# BatteryHullBoard.net
KiCad netlist of a schematic drawn in EAGLE
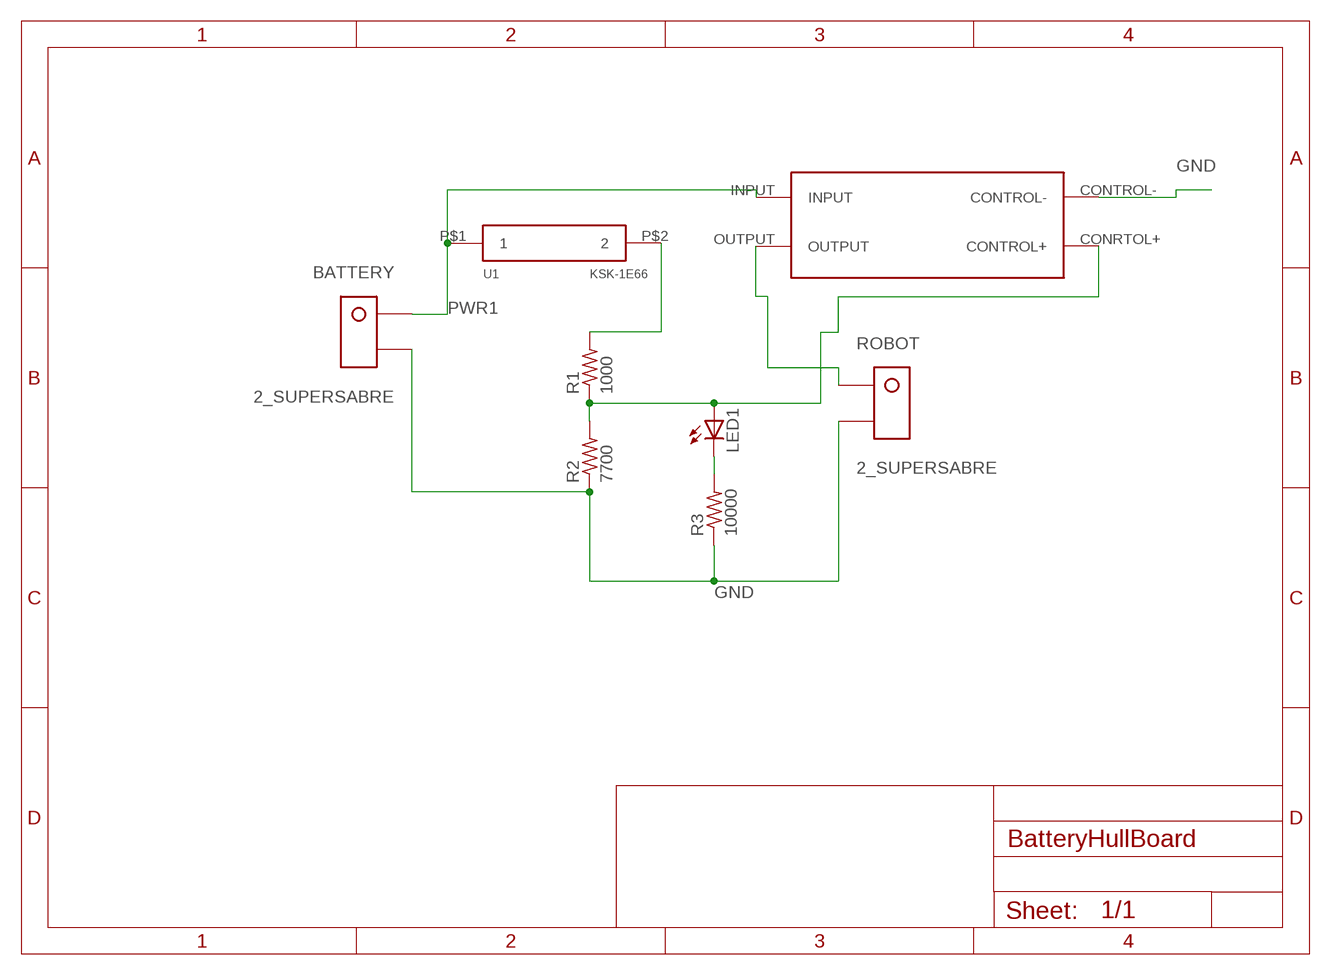
[diagram p0: schematic, sheet 1]

(export (version "E")
  (design (tool "Eeschema 10.0.6"))
  (components
    (comp (ref "BATTERY")
      (value "2_SUPERSABRE")
      (footprint "eagle-import:SUPERSABRE_2CIRCUIT")
      (libsource (lib "eagle-import") (part "2_SUPERSABRE"))
    )
    (comp (ref "LED1")
      (value "LED5MM")
      (footprint "eagle-import:LED5MM")
      (libsource (lib "eagle-import") (part "LED5MM"))
    )
    (comp (ref "R1")
      (value "1000")
      (footprint "eagle-import:R0805")
      (libsource (lib "eagle-import") (part "R-US_R0805"))
    )
    (comp (ref "R2")
      (value "7700")
      (footprint "eagle-import:R0805")
      (libsource (lib "eagle-import") (part "R-US_R0805"))
    )
    (comp (ref "R3")
      (value "10000")
      (footprint "eagle-import:R0805")
      (libsource (lib "eagle-import") (part "R-US_R0805"))
    )
    (comp (ref "ROBOT")
      (value "2_SUPERSABRE")
      (footprint "eagle-import:SUPERSABRE_2CIRCUIT")
      (libsource (lib "eagle-import") (part "2_SUPERSABRE"))
    )
    (comp (ref "U$1")
      (value "ADJH21112")
      (footprint "eagle-import:ADJH21112")
      (libsource (lib "eagle-import") (part "ADJH21112"))
    )
    (comp (ref "U1")
      (value "KSK-1E66")
      (footprint "eagle-import:KSK-1E66")
      (libsource (lib "eagle-import") (part "KSK-1E66"))
    )
  )
  (nets
    (net (code "1") (name "/GND") (class "Default")
      (node (ref "BATTERY") (pin "P$2") (pinfunction "P$2_P$2") (pintype "bidirectional"))
      (node (ref "R2") (pin "1") (pinfunction "1_1") (pintype "passive"))
      (node (ref "R3") (pin "1") (pinfunction "1_1") (pintype "passive"))
      (node (ref "ROBOT") (pin "P$2") (pinfunction "P$2_P$2") (pintype "bidirectional"))
      (node (ref "U$1") (pin "CONTROL-") (pinfunction "CONTROL-_CONTROL-") (pintype "output"))
    )
    (net (code "2") (name "/PWR1") (class "Default")
      (node (ref "BATTERY") (pin "P$1") (pinfunction "P$1_P$1") (pintype "bidirectional"))
      (node (ref "U$1") (pin "INPUT") (pinfunction "INPUT_INPUT") (pintype "input"))
      (node (ref "U1") (pin "P$1") (pinfunction "1_P$1") (pintype "input"))
    )
    (net (code "3") (name "Net-(LED1-C)") (class "Default")
      (node (ref "LED1") (pin "K") (pinfunction "C_K") (pintype "passive"))
      (node (ref "R3") (pin "2") (pinfunction "2_2") (pintype "passive"))
    )
    (net (code "4") (name "Net-(ROBOT-PadP$1)") (class "Default")
      (node (ref "ROBOT") (pin "P$1") (pinfunction "P$1_P$1") (pintype "bidirectional"))
      (node (ref "U$1") (pin "OUTPUT") (pinfunction "OUTPUT_OUTPUT") (pintype "output"))
    )
    (net (code "5") (name "Net-(U$1-CONTROL+)") (class "Default")
      (node (ref "LED1") (pin "A") (pinfunction "A_A") (pintype "passive"))
      (node (ref "R1") (pin "1") (pinfunction "1_1") (pintype "passive"))
      (node (ref "R2") (pin "2") (pinfunction "2_2") (pintype "passive"))
      (node (ref "U$1") (pin "CONRTOL+") (pinfunction "CONTROL+_CONRTOL+") (pintype "input"))
    )
    (net (code "6") (name "Net-(U1-2)") (class "Default")
      (node (ref "R1") (pin "2") (pinfunction "2_2") (pintype "passive"))
      (node (ref "U1") (pin "P$2") (pinfunction "2_P$2") (pintype "output"))
    )
  )
)
